# Sheet1.net
KiCad netlist of a schematic drawn in Altium Designer
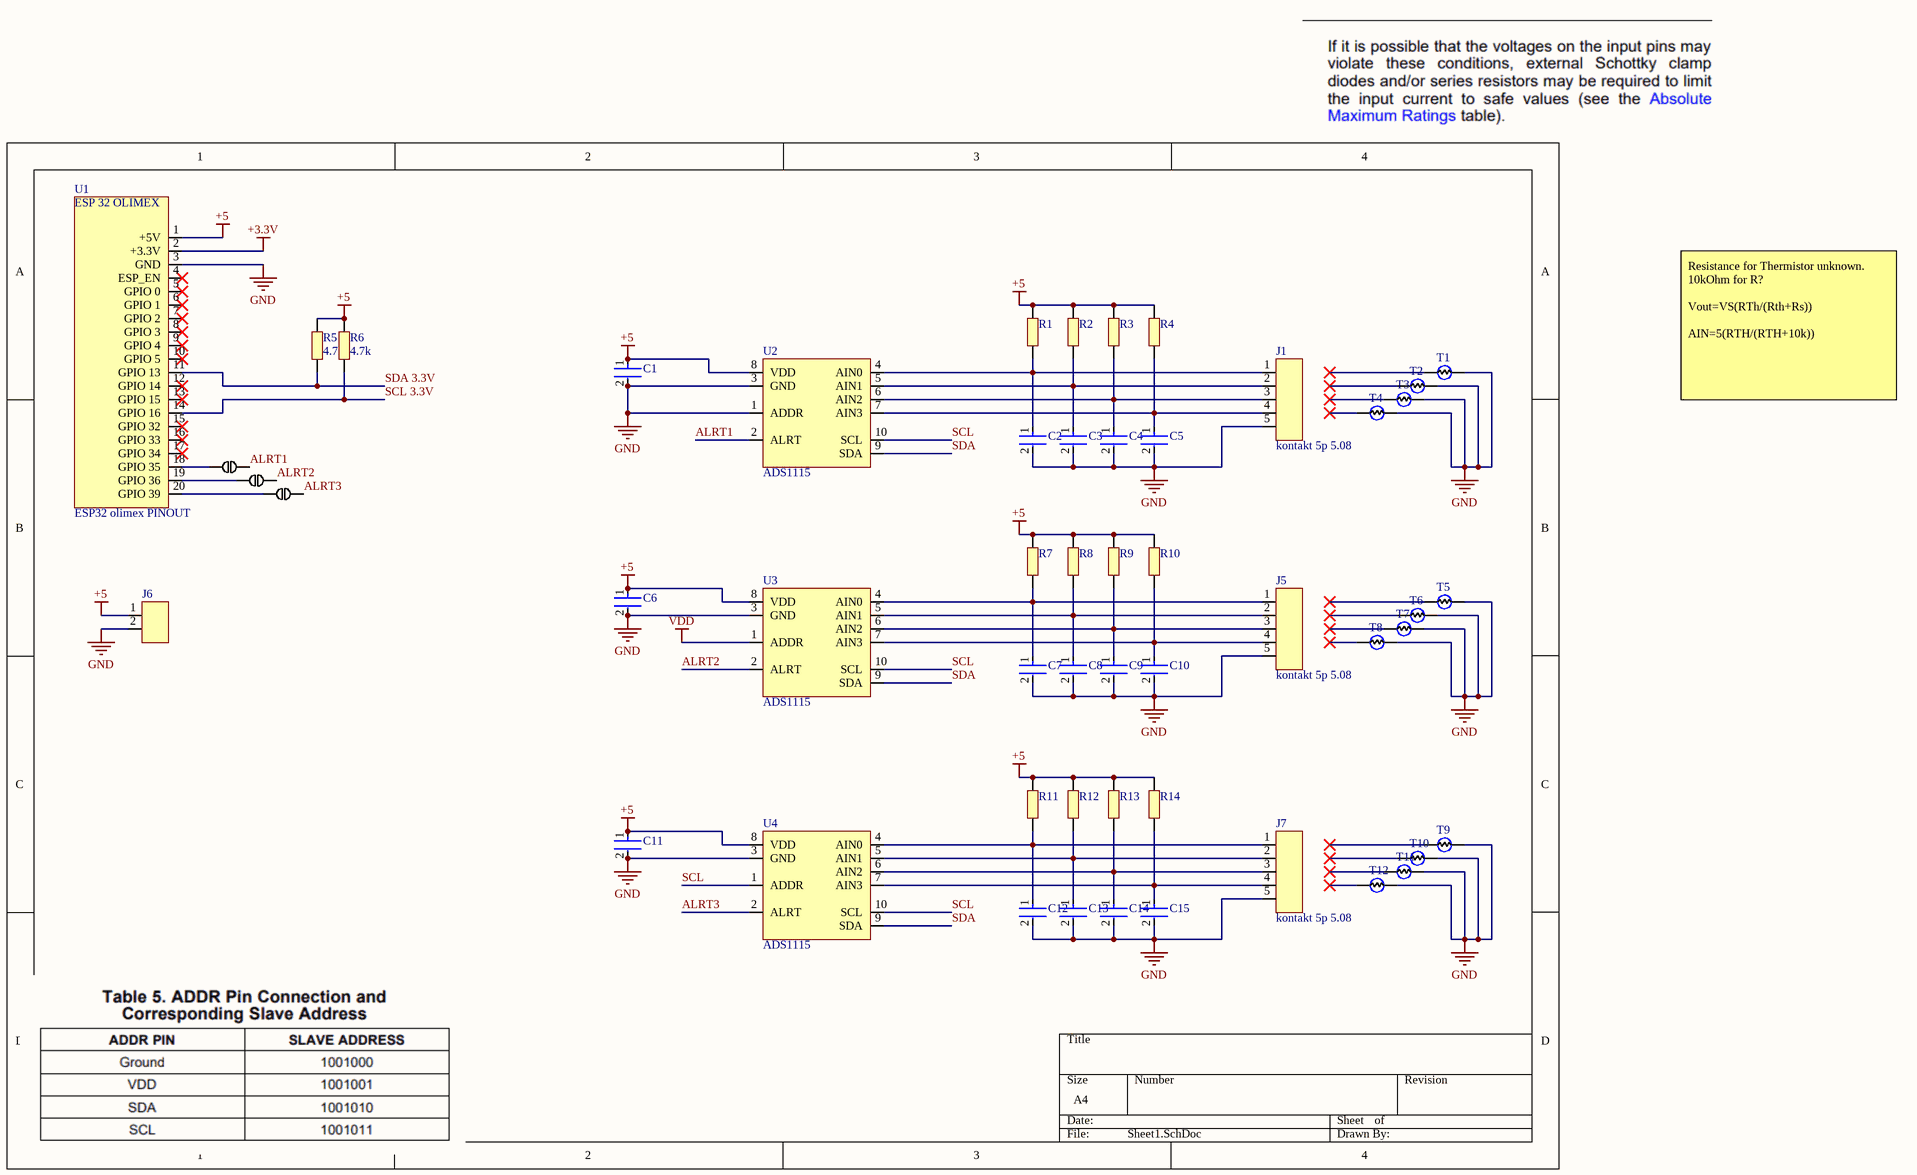
[diagram p0: Sheet1.SchDoc]

(export (version "E")
  (design (tool "Eeschema 10.0.6"))
  (components
    (comp (ref "C1")
      (value "CC0603KRX7R9BB104")
      (footprint "FP-CC0603-DA-MFG")
      (description "CAP CER 0.1UF 50V X7R 0603")
      (fields (field (name "MANUFACTURER") "YAGEO") (field (name "VOLTAGE") "50 V"))
      (libsource (lib "Altium Content Vault") (part "11868f565c42a9108669ba33697ecf6"))
    )
    (comp (ref "C2")
      (value "CL10A106MA8NRNC")
      (footprint "FP-CL10-IPC_C")
      (description "Cap Ceramic 10uF 25V X5R ±20% Pad SMD 0603 +85°C T/R")
      (fields (field (name "TOLERANCE") "20%"))
      (libsource (lib "Altium Content Vault") (part "b4654b650e69147ec39a6b967a45e02"))
    )
    (comp (ref "C3")
      (value "CL10A106MA8NRNC")
      (footprint "FP-CL10-IPC_C")
      (description "Cap Ceramic 10uF 25V X5R ±20% Pad SMD 0603 +85°C T/R")
      (fields (field (name "TOLERANCE") "20%"))
      (libsource (lib "Altium Content Vault") (part "b4654b650e69147ec39a6b967a45e02"))
    )
    (comp (ref "C4")
      (value "CL10A106MA8NRNC")
      (footprint "FP-CL10-IPC_C")
      (description "Cap Ceramic 10uF 25V X5R ±20% Pad SMD 0603 +85°C T/R")
      (fields (field (name "TOLERANCE") "20%"))
      (libsource (lib "Altium Content Vault") (part "b4654b650e69147ec39a6b967a45e02"))
    )
    (comp (ref "C5")
      (value "CL10A106MA8NRNC")
      (footprint "FP-CL10-IPC_C")
      (description "Cap Ceramic 10uF 25V X5R ±20% Pad SMD 0603 +85°C T/R")
      (fields (field (name "TOLERANCE") "20%"))
      (libsource (lib "Altium Content Vault") (part "b4654b650e69147ec39a6b967a45e02"))
    )
    (comp (ref "C6")
      (value "CC0603KRX7R9BB104")
      (footprint "FP-CC0603-DA-MFG")
      (description "CAP CER 0.1UF 50V X7R 0603")
      (fields (field (name "MANUFACTURER") "YAGEO") (field (name "VOLTAGE") "50 V"))
      (libsource (lib "Altium Content Vault") (part "11868f565c42a9108669ba33697ecf6"))
    )
    (comp (ref "C7")
      (value "CL10A106MA8NRNC")
      (footprint "FP-CL10-IPC_C")
      (description "Cap Ceramic 10uF 25V X5R ±20% Pad SMD 0603 +85°C T/R")
      (fields (field (name "TOLERANCE") "20%"))
      (libsource (lib "Altium Content Vault") (part "b4654b650e69147ec39a6b967a45e02"))
    )
    (comp (ref "C8")
      (value "CL10A106MA8NRNC")
      (footprint "FP-CL10-IPC_C")
      (description "Cap Ceramic 10uF 25V X5R ±20% Pad SMD 0603 +85°C T/R")
      (fields (field (name "TOLERANCE") "20%"))
      (libsource (lib "Altium Content Vault") (part "b4654b650e69147ec39a6b967a45e02"))
    )
    (comp (ref "C9")
      (value "CL10A106MA8NRNC")
      (footprint "FP-CL10-IPC_C")
      (description "Cap Ceramic 10uF 25V X5R ±20% Pad SMD 0603 +85°C T/R")
      (fields (field (name "TOLERANCE") "20%"))
      (libsource (lib "Altium Content Vault") (part "b4654b650e69147ec39a6b967a45e02"))
    )
    (comp (ref "C10")
      (value "CL10A106MA8NRNC")
      (footprint "FP-CL10-IPC_C")
      (description "Cap Ceramic 10uF 25V X5R ±20% Pad SMD 0603 +85°C T/R")
      (fields (field (name "TOLERANCE") "20%"))
      (libsource (lib "Altium Content Vault") (part "b4654b650e69147ec39a6b967a45e02"))
    )
    (comp (ref "C11")
      (value "CC0603KRX7R9BB104")
      (footprint "FP-CC0603-DA-MFG")
      (description "CAP CER 0.1UF 50V X7R 0603")
      (fields (field (name "MANUFACTURER") "YAGEO") (field (name "VOLTAGE") "50 V"))
      (libsource (lib "Altium Content Vault") (part "11868f565c42a9108669ba33697ecf6"))
    )
    (comp (ref "C12")
      (value "CL10A106MA8NRNC")
      (footprint "FP-CL10-IPC_C")
      (description "Cap Ceramic 10uF 25V X5R ±20% Pad SMD 0603 +85°C T/R")
      (fields (field (name "TOLERANCE") "20%"))
      (libsource (lib "Altium Content Vault") (part "b4654b650e69147ec39a6b967a45e02"))
    )
    (comp (ref "C13")
      (value "CL10A106MA8NRNC")
      (footprint "FP-CL10-IPC_C")
      (description "Cap Ceramic 10uF 25V X5R ±20% Pad SMD 0603 +85°C T/R")
      (fields (field (name "TOLERANCE") "20%"))
      (libsource (lib "Altium Content Vault") (part "b4654b650e69147ec39a6b967a45e02"))
    )
    (comp (ref "C14")
      (value "CL10A106MA8NRNC")
      (footprint "FP-CL10-IPC_C")
      (description "Cap Ceramic 10uF 25V X5R ±20% Pad SMD 0603 +85°C T/R")
      (fields (field (name "TOLERANCE") "20%"))
      (libsource (lib "Altium Content Vault") (part "b4654b650e69147ec39a6b967a45e02"))
    )
    (comp (ref "C15")
      (value "CL10A106MA8NRNC")
      (footprint "FP-CL10-IPC_C")
      (description "Cap Ceramic 10uF 25V X5R ±20% Pad SMD 0603 +85°C T/R")
      (fields (field (name "TOLERANCE") "20%"))
      (libsource (lib "Altium Content Vault") (part "b4654b650e69147ec39a6b967a45e02"))
    )
    (comp (ref "J1")
      (value "kontakt 5p 5.08")
      (fields
        (field (name "MANUFACTURER") "Ningbo Xinlaiya Elec.")
        (field (name "MANUFACTURER PART NUMBER") "XY2500R-G-3.5-5P")
      )
      (libsource (lib "Schlib1") (part "kontakt 5p 5.08"))
    )
    (comp (ref "J2") (value "Solder jumper") (libsource (lib "Schlib1") (part "Solder jumper")))
    (comp (ref "J3") (value "Solder jumper") (libsource (lib "Schlib1") (part "Solder jumper")))
    (comp (ref "J4") (value "Solder jumper") (libsource (lib "Schlib1") (part "Solder jumper")))
    (comp (ref "J5")
      (value "kontakt 5p 5.08")
      (fields
        (field (name "MANUFACTURER") "Ningbo Xinlaiya Elec.")
        (field (name "MANUFACTURER PART NUMBER") "XY2500R-G-3.5-5P")
      )
      (libsource (lib "Schlib1") (part "kontakt 5p 5.08"))
    )
    (comp (ref "J6")
      (value "kontakt 2p 5.08")
      (fields
        (field (name "MANUFACTURER") "DEGSON")
        (field (name "MANUFACTURER PART NUMBER") "2EDGRC-5.08-02P-14-100A(H)")
      )
      (libsource (lib "Schlib1") (part "kontakt 2p 5.08"))
    )
    (comp (ref "J7")
      (value "kontakt 5p 5.08")
      (fields
        (field (name "MANUFACTURER") "Ningbo Xinlaiya Elec.")
        (field (name "MANUFACTURER PART NUMBER") "XY2500R-G-3.5-5P")
      )
      (libsource (lib "Schlib1") (part "kontakt 5p 5.08"))
    )
    (comp (ref "R1") (value "R0603") (libsource (lib "Schlib1") (part "R0603")))
    (comp (ref "R2") (value "R0603") (libsource (lib "Schlib1") (part "R0603")))
    (comp (ref "R3") (value "R0603") (libsource (lib "Schlib1") (part "R0603")))
    (comp (ref "R4") (value "R0603") (libsource (lib "Schlib1") (part "R0603")))
    (comp (ref "R5")
      (value "4.7k")
      (description "R0603")
      (fields
        (field (name "MANUFACTURER") "Royal Electronic Factory")
        (field (name "MANUFACTURER PART NUMBER") "0603WAF4701T5E")
      )
      (libsource (lib "Schlib1") (part "R0603"))
    )
    (comp (ref "R6")
      (value "4.7k")
      (description "0603")
      (fields
        (field (name "MANUFACTURER") "Royal Electronic Factory")
        (field (name "MANUFACTURER PART NUMBER") "0603WAF4701T5E")
      )
      (libsource (lib "Schlib1") (part "R0603"))
    )
    (comp (ref "R7") (value "R0603") (libsource (lib "Schlib1") (part "R0603")))
    (comp (ref "R8") (value "R0603") (libsource (lib "Schlib1") (part "R0603")))
    (comp (ref "R9") (value "R0603") (libsource (lib "Schlib1") (part "R0603")))
    (comp (ref "R10") (value "R0603") (libsource (lib "Schlib1") (part "R0603")))
    (comp (ref "R11") (value "R0603") (libsource (lib "Schlib1") (part "R0603")))
    (comp (ref "R12") (value "R0603") (libsource (lib "Schlib1") (part "R0603")))
    (comp (ref "R13") (value "R0603") (libsource (lib "Schlib1") (part "R0603")))
    (comp (ref "R14") (value "R0603") (libsource (lib "Schlib1") (part "R0603")))
    (comp (ref "T1")
      (value "thermistor")
      (description "2.8kOhm")
      (libsource (lib "Schlib1") (part "thermistor"))
    )
    (comp (ref "T2")
      (value "thermistor")
      (description "2.8kOhm")
      (libsource (lib "Schlib1") (part "thermistor"))
    )
    (comp (ref "T3")
      (value "thermistor")
      (description "2.8kOhm")
      (libsource (lib "Schlib1") (part "thermistor"))
    )
    (comp (ref "T4")
      (value "thermistor")
      (description "2.8kOhm")
      (libsource (lib "Schlib1") (part "thermistor"))
    )
    (comp (ref "T5")
      (value "thermistor")
      (description "2.8kOhm")
      (libsource (lib "Schlib1") (part "thermistor"))
    )
    (comp (ref "T6")
      (value "thermistor")
      (description "2.8kOhm")
      (libsource (lib "Schlib1") (part "thermistor"))
    )
    (comp (ref "T7")
      (value "thermistor")
      (description "2.8kOhm")
      (libsource (lib "Schlib1") (part "thermistor"))
    )
    (comp (ref "T8")
      (value "thermistor")
      (description "2.8kOhm")
      (libsource (lib "Schlib1") (part "thermistor"))
    )
    (comp (ref "T9")
      (value "thermistor")
      (description "2.8kOhm")
      (libsource (lib "Schlib1") (part "thermistor"))
    )
    (comp (ref "T10")
      (value "thermistor")
      (description "2.8kOhm")
      (libsource (lib "Schlib1") (part "thermistor"))
    )
    (comp (ref "T11")
      (value "thermistor")
      (description "2.8kOhm")
      (libsource (lib "Schlib1") (part "thermistor"))
    )
    (comp (ref "T12")
      (value "thermistor")
      (description "2.8kOhm")
      (libsource (lib "Schlib1") (part "thermistor"))
    )
    (comp (ref "U1")
      (value "ESP32 olimex PINOUT")
      (footprint "ESP32 OLIMEX POE")
      (libsource (lib "Schlib1") (part "ESP32 olimex PINOUT"))
    )
    (comp (ref "U2")
      (value "ADS1115")
      (footprint "TSSOP50P490X110-10N ADS1115")
      (description "4-Channel Single ADC Delta-Sigma 860sps 16-bit Serial 10-Pin VSSOP T/R")
      (fields
        (field (name "MANUFACTURER") "Texas Instruments")
        (field (name "MANUFACTURER PART NUMBER") "ADS1115IDGSR")
      )
      (libsource (lib "Schlib1") (part "ADS1113"))
    )
    (comp (ref "U3")
      (value "ADS1115")
      (footprint "TSSOP50P490X110-10N ADS1115")
      (description "4-Channel Single ADC Delta-Sigma 860sps 16-bit Serial 10-Pin VSSOP T/R")
      (fields
        (field (name "MANUFACTURER") "Texas Instruments")
        (field (name "MANUFACTURER PART NUMBER") "ADS1115IDGSR")
      )
      (libsource (lib "Schlib1") (part "ADS1113"))
    )
    (comp (ref "U4")
      (value "ADS1115")
      (footprint "TSSOP50P490X110-10N ADS1115")
      (description "4-Channel Single ADC Delta-Sigma 860sps 16-bit Serial 10-Pin VSSOP T/R")
      (fields
        (field (name "MANUFACTURER") "Texas Instruments")
        (field (name "MANUFACTURER PART NUMBER") "ADS1115IDGSR")
      )
      (libsource (lib "Schlib1") (part "ADS1113"))
    )
  )
  (nets
    (net (code "1") (name "+3.3V") (class "Default")
      (node (ref "U1") (pin "2") (pinfunction "+3.3V_2") (pintype "passive"))
    )
    (net (code "2") (name "+5") (class "Default")
      (node (ref "C1") (pin "1") (pinfunction "1_1") (pintype "passive"))
      (node (ref "C11") (pin "1") (pinfunction "1_1") (pintype "passive"))
      (node (ref "C6") (pin "1") (pinfunction "1_1") (pintype "passive"))
      (node (ref "J6") (pin "1") (pinfunction "1_1") (pintype "passive"))
      (node (ref "R1") (pin "2") (pinfunction "2_2") (pintype "passive"))
      (node (ref "R10") (pin "2") (pinfunction "2_2") (pintype "passive"))
      (node (ref "R11") (pin "2") (pinfunction "2_2") (pintype "passive"))
      (node (ref "R12") (pin "2") (pinfunction "2_2") (pintype "passive"))
      (node (ref "R13") (pin "2") (pinfunction "2_2") (pintype "passive"))
      (node (ref "R14") (pin "2") (pinfunction "2_2") (pintype "passive"))
      (node (ref "R2") (pin "2") (pinfunction "2_2") (pintype "passive"))
      (node (ref "R3") (pin "2") (pinfunction "2_2") (pintype "passive"))
      (node (ref "R4") (pin "2") (pinfunction "2_2") (pintype "passive"))
      (node (ref "R5") (pin "2") (pinfunction "2_2") (pintype "passive"))
      (node (ref "R6") (pin "2") (pinfunction "2_2") (pintype "passive"))
      (node (ref "R7") (pin "2") (pinfunction "2_2") (pintype "passive"))
      (node (ref "R8") (pin "2") (pinfunction "2_2") (pintype "passive"))
      (node (ref "R9") (pin "2") (pinfunction "2_2") (pintype "passive"))
      (node (ref "U1") (pin "1") (pinfunction "+5V_1") (pintype "passive"))
      (node (ref "U2") (pin "8") (pinfunction "VDD_8") (pintype "passive"))
      (node (ref "U3") (pin "8") (pinfunction "VDD_8") (pintype "passive"))
      (node (ref "U4") (pin "8") (pinfunction "VDD_8") (pintype "passive"))
    )
    (net (code "3") (name "/ALRT1") (class "Default")
      (node (ref "J2") (pin "24") (pinfunction "24_24") (pintype "passive"))
      (node (ref "U2") (pin "2") (pinfunction "ALRT_2") (pintype "passive"))
    )
    (net (code "4") (name "/ALRT2") (class "Default")
      (node (ref "J3") (pin "24") (pinfunction "24_24") (pintype "passive"))
      (node (ref "U3") (pin "2") (pinfunction "ALRT_2") (pintype "passive"))
    )
    (net (code "5") (name "/ALRT3") (class "Default")
      (node (ref "J4") (pin "24") (pinfunction "24_24") (pintype "passive"))
      (node (ref "U4") (pin "2") (pinfunction "ALRT_2") (pintype "passive"))
    )
    (net (code "6") (name "/SCL") (class "Default")
      (node (ref "U2") (pin "10") (pinfunction "SCL_10") (pintype "passive"))
      (node (ref "U3") (pin "10") (pinfunction "SCL_10") (pintype "passive"))
      (node (ref "U4") (pin "1") (pinfunction "ADDR_1") (pintype "passive"))
      (node (ref "U4") (pin "10") (pinfunction "SCL_10") (pintype "passive"))
    )
    (net (code "7") (name "/SCL 3.3V") (class "Default")
      (node (ref "R6") (pin "1") (pinfunction "1_1") (pintype "passive"))
      (node (ref "U1") (pin "14") (pinfunction "GPIO_16_14") (pintype "passive"))
    )
    (net (code "8") (name "/SDA") (class "Default")
      (node (ref "U2") (pin "9") (pinfunction "SDA_9") (pintype "passive"))
      (node (ref "U3") (pin "9") (pinfunction "SDA_9") (pintype "passive"))
      (node (ref "U4") (pin "9") (pinfunction "SDA_9") (pintype "passive"))
    )
    (net (code "9") (name "/SDA 3.3V") (class "Default")
      (node (ref "R5") (pin "1") (pinfunction "1_1") (pintype "passive"))
      (node (ref "U1") (pin "11") (pinfunction "GPIO_13_11") (pintype "passive"))
    )
    (net (code "10") (name "GND") (class "Default")
      (node (ref "C1") (pin "2") (pinfunction "2_2") (pintype "passive"))
      (node (ref "C10") (pin "2") (pinfunction "2_2") (pintype "passive"))
      (node (ref "C11") (pin "2") (pinfunction "2_2") (pintype "passive"))
      (node (ref "C12") (pin "2") (pinfunction "2_2") (pintype "passive"))
      (node (ref "C13") (pin "2") (pinfunction "2_2") (pintype "passive"))
      (node (ref "C14") (pin "2") (pinfunction "2_2") (pintype "passive"))
      (node (ref "C15") (pin "2") (pinfunction "2_2") (pintype "passive"))
      (node (ref "C2") (pin "2") (pinfunction "2_2") (pintype "passive"))
      (node (ref "C3") (pin "2") (pinfunction "2_2") (pintype "passive"))
      (node (ref "C4") (pin "2") (pinfunction "2_2") (pintype "passive"))
      (node (ref "C5") (pin "2") (pinfunction "2_2") (pintype "passive"))
      (node (ref "C6") (pin "2") (pinfunction "2_2") (pintype "passive"))
      (node (ref "C7") (pin "2") (pinfunction "2_2") (pintype "passive"))
      (node (ref "C8") (pin "2") (pinfunction "2_2") (pintype "passive"))
      (node (ref "C9") (pin "2") (pinfunction "2_2") (pintype "passive"))
      (node (ref "J1") (pin "5") (pinfunction "5_5") (pintype "passive"))
      (node (ref "J5") (pin "5") (pinfunction "5_5") (pintype "passive"))
      (node (ref "J6") (pin "2") (pinfunction "2_2") (pintype "passive"))
      (node (ref "J7") (pin "5") (pinfunction "5_5") (pintype "passive"))
      (node (ref "T1") (pin "2") (pinfunction "11_2") (pintype "passive"))
      (node (ref "T10") (pin "2") (pinfunction "11_2") (pintype "passive"))
      (node (ref "T11") (pin "2") (pinfunction "11_2") (pintype "passive"))
      (node (ref "T12") (pin "2") (pinfunction "11_2") (pintype "passive"))
      (node (ref "T2") (pin "2") (pinfunction "11_2") (pintype "passive"))
      (node (ref "T3") (pin "2") (pinfunction "11_2") (pintype "passive"))
      (node (ref "T4") (pin "2") (pinfunction "11_2") (pintype "passive"))
      (node (ref "T5") (pin "2") (pinfunction "11_2") (pintype "passive"))
      (node (ref "T6") (pin "2") (pinfunction "11_2") (pintype "passive"))
      (node (ref "T7") (pin "2") (pinfunction "11_2") (pintype "passive"))
      (node (ref "T8") (pin "2") (pinfunction "11_2") (pintype "passive"))
      (node (ref "T9") (pin "2") (pinfunction "11_2") (pintype "passive"))
      (node (ref "U1") (pin "3") (pinfunction "GND_3") (pintype "passive"))
      (node (ref "U2") (pin "1") (pinfunction "ADDR_1") (pintype "passive"))
      (node (ref "U2") (pin "3") (pinfunction "GND_3") (pintype "passive"))
      (node (ref "U3") (pin "3") (pinfunction "GND_3") (pintype "passive"))
      (node (ref "U4") (pin "3") (pinfunction "GND_3") (pintype "passive"))
    )
    (net (code "11") (name "Net-(U1-GPIO_35)") (class "Default")
      (node (ref "J2") (pin "23") (pinfunction "23_23") (pintype "passive"))
      (node (ref "U1") (pin "18") (pinfunction "GPIO_35_18") (pintype "passive"))
    )
    (net (code "12") (name "Net-(U1-GPIO_36)") (class "Default")
      (node (ref "J3") (pin "23") (pinfunction "23_23") (pintype "passive"))
      (node (ref "U1") (pin "19") (pinfunction "GPIO_36_19") (pintype "passive"))
    )
    (net (code "13") (name "Net-(U1-GPIO_39)") (class "Default")
      (node (ref "J4") (pin "23") (pinfunction "23_23") (pintype "passive"))
      (node (ref "U1") (pin "20") (pinfunction "GPIO_39_20") (pintype "passive"))
    )
    (net (code "14") (name "Net-(U2-AIN0)") (class "Default")
      (node (ref "C2") (pin "1") (pinfunction "1_1") (pintype "passive"))
      (node (ref "J1") (pin "1") (pinfunction "1_1") (pintype "passive"))
      (node (ref "R1") (pin "1") (pinfunction "1_1") (pintype "passive"))
      (node (ref "U2") (pin "4") (pinfunction "AIN0_4") (pintype "passive"))
    )
    (net (code "15") (name "Net-(U2-AIN1)") (class "Default")
      (node (ref "C3") (pin "1") (pinfunction "1_1") (pintype "passive"))
      (node (ref "J1") (pin "2") (pinfunction "2_2") (pintype "passive"))
      (node (ref "R2") (pin "1") (pinfunction "1_1") (pintype "passive"))
      (node (ref "U2") (pin "5") (pinfunction "AIN1_5") (pintype "passive"))
    )
    (net (code "16") (name "Net-(U2-AIN2)") (class "Default")
      (node (ref "C4") (pin "1") (pinfunction "1_1") (pintype "passive"))
      (node (ref "J1") (pin "3") (pinfunction "3_3") (pintype "passive"))
      (node (ref "R3") (pin "1") (pinfunction "1_1") (pintype "passive"))
      (node (ref "U2") (pin "6") (pinfunction "AIN2_6") (pintype "passive"))
    )
    (net (code "17") (name "Net-(U2-AIN3)") (class "Default")
      (node (ref "C5") (pin "1") (pinfunction "1_1") (pintype "passive"))
      (node (ref "J1") (pin "4") (pinfunction "4_4") (pintype "passive"))
      (node (ref "R4") (pin "1") (pinfunction "1_1") (pintype "passive"))
      (node (ref "U2") (pin "7") (pinfunction "AIN3_7") (pintype "passive"))
    )
    (net (code "18") (name "Net-(U3-AIN0)") (class "Default")
      (node (ref "C7") (pin "1") (pinfunction "1_1") (pintype "passive"))
      (node (ref "J5") (pin "1") (pinfunction "1_1") (pintype "passive"))
      (node (ref "R7") (pin "1") (pinfunction "1_1") (pintype "passive"))
      (node (ref "U3") (pin "4") (pinfunction "AIN0_4") (pintype "passive"))
    )
    (net (code "19") (name "Net-(U3-AIN1)") (class "Default")
      (node (ref "C8") (pin "1") (pinfunction "1_1") (pintype "passive"))
      (node (ref "J5") (pin "2") (pinfunction "2_2") (pintype "passive"))
      (node (ref "R8") (pin "1") (pinfunction "1_1") (pintype "passive"))
      (node (ref "U3") (pin "5") (pinfunction "AIN1_5") (pintype "passive"))
    )
    (net (code "20") (name "Net-(U3-AIN2)") (class "Default")
      (node (ref "C9") (pin "1") (pinfunction "1_1") (pintype "passive"))
      (node (ref "J5") (pin "3") (pinfunction "3_3") (pintype "passive"))
      (node (ref "R9") (pin "1") (pinfunction "1_1") (pintype "passive"))
      (node (ref "U3") (pin "6") (pinfunction "AIN2_6") (pintype "passive"))
    )
    (net (code "21") (name "Net-(U3-AIN3)") (class "Default")
      (node (ref "C10") (pin "1") (pinfunction "1_1") (pintype "passive"))
      (node (ref "J5") (pin "4") (pinfunction "4_4") (pintype "passive"))
      (node (ref "R10") (pin "1") (pinfunction "1_1") (pintype "passive"))
      (node (ref "U3") (pin "7") (pinfunction "AIN3_7") (pintype "passive"))
    )
    (net (code "22") (name "Net-(U4-AIN0)") (class "Default")
      (node (ref "C12") (pin "1") (pinfunction "1_1") (pintype "passive"))
      (node (ref "J7") (pin "1") (pinfunction "1_1") (pintype "passive"))
      (node (ref "R11") (pin "1") (pinfunction "1_1") (pintype "passive"))
      (node (ref "U4") (pin "4") (pinfunction "AIN0_4") (pintype "passive"))
    )
    (net (code "23") (name "Net-(U4-AIN1)") (class "Default")
      (node (ref "C13") (pin "1") (pinfunction "1_1") (pintype "passive"))
      (node (ref "J7") (pin "2") (pinfunction "2_2") (pintype "passive"))
      (node (ref "R12") (pin "1") (pinfunction "1_1") (pintype "passive"))
      (node (ref "U4") (pin "5") (pinfunction "AIN1_5") (pintype "passive"))
    )
    (net (code "24") (name "Net-(U4-AIN2)") (class "Default")
      (node (ref "C14") (pin "1") (pinfunction "1_1") (pintype "passive"))
      (node (ref "J7") (pin "3") (pinfunction "3_3") (pintype "passive"))
      (node (ref "R13") (pin "1") (pinfunction "1_1") (pintype "passive"))
      (node (ref "U4") (pin "6") (pinfunction "AIN2_6") (pintype "passive"))
    )
    (net (code "25") (name "Net-(U4-AIN3)") (class "Default")
      (node (ref "C15") (pin "1") (pinfunction "1_1") (pintype "passive"))
      (node (ref "J7") (pin "4") (pinfunction "4_4") (pintype "passive"))
      (node (ref "R14") (pin "1") (pinfunction "1_1") (pintype "passive"))
      (node (ref "U4") (pin "7") (pinfunction "AIN3_7") (pintype "passive"))
    )
    (net (code "26") (name "VDD") (class "Default")
      (node (ref "U3") (pin "1") (pinfunction "ADDR_1") (pintype "passive"))
    )
    (net (code "27") (name "unconnected-(T1-Pad1)") (class "Default")
      (node (ref "T1") (pin "1") (pinfunction "1_1") (pintype "passive+no_connect"))
    )
    (net (code "28") (name "unconnected-(T2-Pad1)") (class "Default")
      (node (ref "T2") (pin "1") (pinfunction "1_1") (pintype "passive+no_connect"))
    )
    (net (code "29") (name "unconnected-(T3-Pad1)") (class "Default")
      (node (ref "T3") (pin "1") (pinfunction "1_1") (pintype "passive+no_connect"))
    )
    (net (code "30") (name "unconnected-(T4-Pad1)") (class "Default")
      (node (ref "T4") (pin "1") (pinfunction "1_1") (pintype "passive+no_connect"))
    )
    (net (code "31") (name "unconnected-(T5-Pad1)") (class "Default")
      (node (ref "T5") (pin "1") (pinfunction "1_1") (pintype "passive+no_connect"))
    )
    (net (code "32") (name "unconnected-(T6-Pad1)") (class "Default")
      (node (ref "T6") (pin "1") (pinfunction "1_1") (pintype "passive+no_connect"))
    )
    (net (code "33") (name "unconnected-(T7-Pad1)") (class "Default")
      (node (ref "T7") (pin "1") (pinfunction "1_1") (pintype "passive+no_connect"))
    )
    (net (code "34") (name "unconnected-(T8-Pad1)") (class "Default")
      (node (ref "T8") (pin "1") (pinfunction "1_1") (pintype "passive+no_connect"))
    )
    (net (code "35") (name "unconnected-(T9-Pad1)") (class "Default")
      (node (ref "T9") (pin "1") (pinfunction "1_1") (pintype "passive+no_connect"))
    )
    (net (code "36") (name "unconnected-(T10-Pad1)") (class "Default")
      (node (ref "T10") (pin "1") (pinfunction "1_1") (pintype "passive+no_connect"))
    )
    (net (code "37") (name "unconnected-(T11-Pad1)") (class "Default")
      (node (ref "T11") (pin "1") (pinfunction "1_1") (pintype "passive+no_connect"))
    )
    (net (code "38") (name "unconnected-(T12-Pad1)") (class "Default")
      (node (ref "T12") (pin "1") (pinfunction "1_1") (pintype "passive+no_connect"))
    )
    (net (code "39") (name "unconnected-(U1-ESP_EN-Pad4)") (class "Default")
      (node (ref "U1") (pin "4") (pinfunction "ESP_EN_4") (pintype "passive+no_connect"))
    )
    (net (code "40") (name "unconnected-(U1-GPIO_0-Pad5)") (class "Default")
      (node (ref "U1") (pin "5") (pinfunction "GPIO_0_5") (pintype "passive+no_connect"))
    )
    (net (code "41") (name "unconnected-(U1-GPIO_1-Pad6)") (class "Default")
      (node (ref "U1") (pin "6") (pinfunction "GPIO_1_6") (pintype "passive+no_connect"))
    )
    (net (code "42") (name "unconnected-(U1-GPIO_2-Pad7)") (class "Default")
      (node (ref "U1") (pin "7") (pinfunction "GPIO_2_7") (pintype "passive+no_connect"))
    )
    (net (code "43") (name "unconnected-(U1-GPIO_3-Pad8)") (class "Default")
      (node (ref "U1") (pin "8") (pinfunction "GPIO_3_8") (pintype "passive+no_connect"))
    )
    (net (code "44") (name "unconnected-(U1-GPIO_4-Pad9)") (class "Default")
      (node (ref "U1") (pin "9") (pinfunction "GPIO_4_9") (pintype "passive+no_connect"))
    )
    (net (code "45") (name "unconnected-(U1-GPIO_5-Pad10)") (class "Default")
      (node (ref "U1") (pin "10") (pinfunction "GPIO_5_10") (pintype "passive+no_connect"))
    )
    (net (code "46") (name "unconnected-(U1-GPIO_14-Pad12)") (class "Default")
      (node (ref "U1") (pin "12") (pinfunction "GPIO_14_12") (pintype "passive+no_connect"))
    )
    (net (code "47") (name "unconnected-(U1-GPIO_15-Pad13)") (class "Default")
      (node (ref "U1") (pin "13") (pinfunction "GPIO_15_13") (pintype "passive+no_connect"))
    )
    (net (code "48") (name "unconnected-(U1-GPIO_32-Pad15)") (class "Default")
      (node (ref "U1") (pin "15") (pinfunction "GPIO_32_15") (pintype "passive+no_connect"))
    )
    (net (code "49") (name "unconnected-(U1-GPIO_33-Pad16)") (class "Default")
      (node (ref "U1") (pin "16") (pinfunction "GPIO_33_16") (pintype "passive+no_connect"))
    )
    (net (code "50") (name "unconnected-(U1-GPIO_34-Pad17)") (class "Default")
      (node (ref "U1") (pin "17") (pinfunction "GPIO_34_17") (pintype "passive+no_connect"))
    )
  )
)
